# breakout.net
KiCad netlist of a schematic drawn in EAGLE
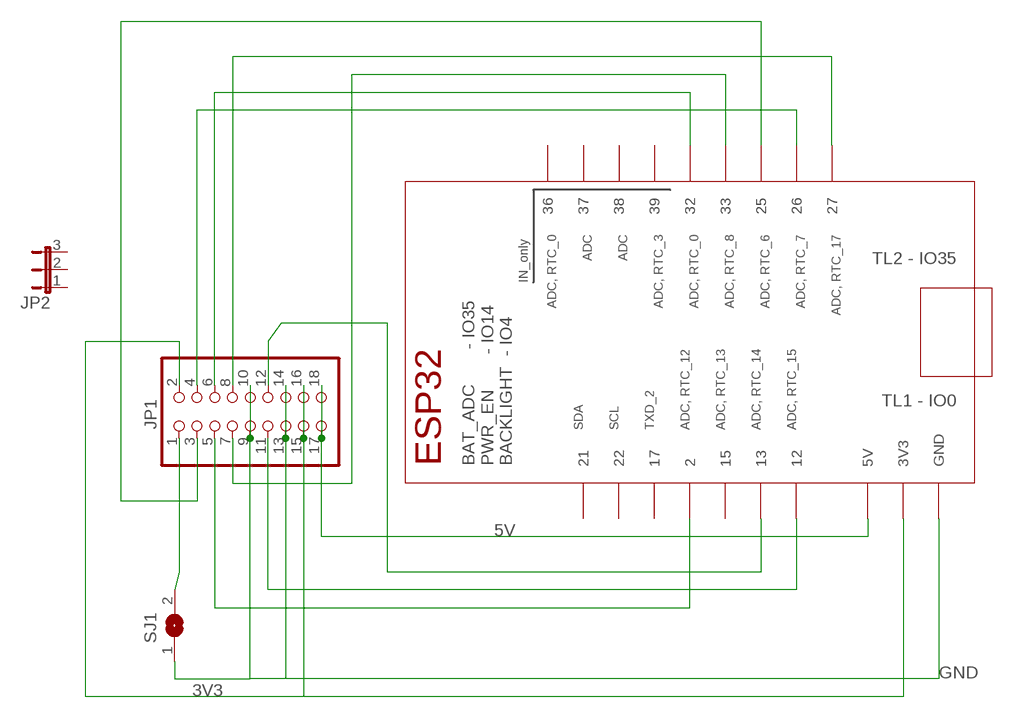
[diagram p0: schematic, sheet 1]

(export (version "E")
  (design (tool "Eeschema 10.0.6"))
  (components
    (comp (ref "IC1")
      (value "TTGO_DISP")
      (footprint "eagle-import:TTGO_DISP_DEFAULT")
      (libsource (lib "eagle-import") (part "TTGO_DISP"))
    )
    (comp (ref "JP1")
      (value "PINHD-2X9-BIG")
      (footprint "eagle-import:2X09-BIG")
      (libsource (lib "eagle-import") (part "PINHD-2X9-BIG"))
    )
    (comp (ref "JP2")
      (value "JUMPER3")
      (footprint "eagle-import:JUMPER3")
      (libsource (lib "eagle-import") (part "JUMPER3"))
    )
    (comp (ref "SJ1")
      (value "SOLDERJUMPERREFLOW")
      (footprint "eagle-import:SOLDERJUMPER_REFLOW")
      (libsource (lib "eagle-import") (part "SOLDERJUMPERREFLOW"))
    )
  )
  (nets
    (net (code "1") (name "/3V3") (class "Default")
      (node (ref "IC1") (pin "3V3_1") (pinfunction "3V3_3V3_1") (pintype "bidirectional"))
      (node (ref "IC1") (pin "3V3_2") (pinfunction "3V3_3V3_2") (pintype "bidirectional"))
      (node (ref "JP1") (pin "15") (pinfunction "15_15") (pintype "passive"))
      (node (ref "JP1") (pin "16") (pinfunction "16_16") (pintype "passive"))
      (node (ref "JP1") (pin "2") (pinfunction "2_2") (pintype "passive"))
    )
    (net (code "2") (name "/5V") (class "Default")
      (node (ref "IC1") (pin "5V") (pinfunction "5V_5V") (pintype "bidirectional"))
      (node (ref "JP1") (pin "17") (pinfunction "17_17") (pintype "passive"))
      (node (ref "JP1") (pin "18") (pinfunction "18_18") (pintype "passive"))
    )
    (net (code "3") (name "/GND") (class "Default")
      (node (ref "IC1") (pin "GND_1") (pinfunction "GND_GND_1") (pintype "bidirectional"))
      (node (ref "IC1") (pin "GND_2") (pinfunction "GND_GND_2") (pintype "bidirectional"))
      (node (ref "IC1") (pin "GND_3") (pinfunction "GND_GND_3") (pintype "bidirectional"))
      (node (ref "IC1") (pin "GND_4") (pinfunction "GND_GND_4") (pintype "bidirectional"))
      (node (ref "IC1") (pin "GND_5") (pinfunction "GND_GND_5") (pintype "bidirectional"))
      (node (ref "JP1") (pin "10") (pinfunction "10_10") (pintype "passive"))
      (node (ref "JP1") (pin "13") (pinfunction "13_13") (pintype "passive"))
      (node (ref "JP1") (pin "14") (pinfunction "14_14") (pintype "passive"))
      (node (ref "JP1") (pin "9") (pinfunction "9_9") (pintype "passive"))
      (node (ref "SJ1") (pin "1") (pinfunction "1_1") (pintype "passive"))
    )
    (net (code "4") (name "Net-(IC1-Pad2)") (class "Default")
      (node (ref "IC1") (pin "2") (pinfunction "2_2") (pintype "bidirectional"))
      (node (ref "JP1") (pin "5") (pinfunction "5_5") (pintype "passive"))
    )
    (net (code "5") (name "Net-(IC1-Pad12)") (class "Default")
      (node (ref "IC1") (pin "12") (pinfunction "12_12") (pintype "bidirectional"))
      (node (ref "JP1") (pin "11") (pinfunction "11_11") (pintype "passive"))
    )
    (net (code "6") (name "Net-(IC1-Pad13)") (class "Default")
      (node (ref "IC1") (pin "13") (pinfunction "13_13") (pintype "bidirectional"))
      (node (ref "JP1") (pin "12") (pinfunction "12_12") (pintype "passive"))
    )
    (net (code "7") (name "Net-(IC1-Pad25)") (class "Default")
      (node (ref "IC1") (pin "25") (pinfunction "25_25") (pintype "bidirectional"))
      (node (ref "JP1") (pin "3") (pinfunction "3_3") (pintype "passive"))
    )
    (net (code "8") (name "Net-(IC1-Pad26)") (class "Default")
      (node (ref "IC1") (pin "26") (pinfunction "26_26") (pintype "bidirectional"))
      (node (ref "JP1") (pin "4") (pinfunction "4_4") (pintype "passive"))
    )
    (net (code "9") (name "Net-(IC1-Pad27)") (class "Default")
      (node (ref "IC1") (pin "27") (pinfunction "27_27") (pintype "bidirectional"))
      (node (ref "JP1") (pin "8") (pinfunction "8_8") (pintype "passive"))
    )
    (net (code "10") (name "Net-(IC1-Pad32)") (class "Default")
      (node (ref "IC1") (pin "32") (pinfunction "32_32") (pintype "bidirectional"))
      (node (ref "JP1") (pin "6") (pinfunction "6_6") (pintype "passive"))
    )
    (net (code "11") (name "Net-(IC1-Pad33)") (class "Default")
      (node (ref "IC1") (pin "33") (pinfunction "33_33") (pintype "bidirectional"))
      (node (ref "JP1") (pin "7") (pinfunction "7_7") (pintype "passive"))
    )
    (net (code "12") (name "Net-(JP1-Pad1)") (class "Default")
      (node (ref "JP1") (pin "1") (pinfunction "1_1") (pintype "passive"))
      (node (ref "SJ1") (pin "2") (pinfunction "2_2") (pintype "passive"))
    )
    (net (code "13") (name "unconnected-(IC1-Pad15)") (class "Default")
      (node (ref "IC1") (pin "15") (pinfunction "15_15") (pintype "bidirectional"))
    )
    (net (code "14") (name "unconnected-(IC1-Pad17)") (class "Default")
      (node (ref "IC1") (pin "17") (pinfunction "17_17") (pintype "bidirectional"))
    )
    (net (code "15") (name "unconnected-(IC1-Pad21)") (class "Default")
      (node (ref "IC1") (pin "21") (pinfunction "21_21") (pintype "bidirectional"))
    )
    (net (code "16") (name "unconnected-(IC1-Pad22)") (class "Default")
      (node (ref "IC1") (pin "22") (pinfunction "22_22") (pintype "bidirectional"))
    )
    (net (code "17") (name "unconnected-(IC1-Pad36)") (class "Default")
      (node (ref "IC1") (pin "36") (pinfunction "36_36") (pintype "bidirectional"))
    )
    (net (code "18") (name "unconnected-(IC1-Pad37)") (class "Default")
      (node (ref "IC1") (pin "37") (pinfunction "37_37") (pintype "bidirectional"))
    )
    (net (code "19") (name "unconnected-(IC1-Pad38)") (class "Default")
      (node (ref "IC1") (pin "38") (pinfunction "38_38") (pintype "bidirectional"))
    )
    (net (code "20") (name "unconnected-(IC1-Pad39)") (class "Default")
      (node (ref "IC1") (pin "39") (pinfunction "39_39") (pintype "bidirectional"))
    )
    (net (code "21") (name "unconnected-(JP2-Pad1)") (class "Default")
      (node (ref "JP2") (pin "1") (pinfunction "1_1") (pintype "passive"))
    )
    (net (code "22") (name "unconnected-(JP2-Pad2)") (class "Default")
      (node (ref "JP2") (pin "2") (pinfunction "2_2") (pintype "passive"))
    )
    (net (code "23") (name "unconnected-(JP2-Pad3)") (class "Default")
      (node (ref "JP2") (pin "3") (pinfunction "3_3") (pintype "passive"))
    )
  )
)
